# Amplificador.net
KiCad netlist of a schematic drawn in Altium Designer
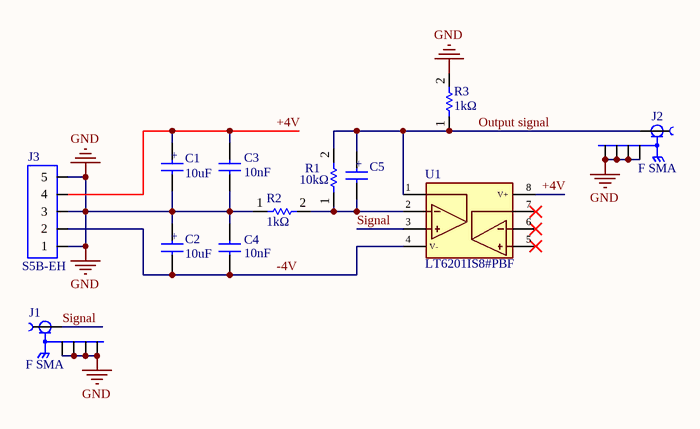
[diagram p0: Amplificador.SchDoc]

(export (version "E")
  (design (tool "Eeschema 10.0.6"))
  (components
    (comp (ref "C1")
      (value "10uF")
      (footprint "WCAP-ATG5_5X11(DXL)")
      (description "10 µF 25 V Aluminum Electrolytic Capacitors Radial, Can 2000 Hrs @ 105°C")
      (libsource (lib "860020472003") (part "WCAP-ATG5_5X11"))
    )
    (comp (ref "C2")
      (value "10uF")
      (footprint "WCAP-ATG5_5X11(DXL)")
      (description "10 µF 25 V Aluminum Electrolytic Capacitors Radial, Can 2000 Hrs @ 105°C")
      (libsource (lib "860020472003") (part "WCAP-ATG5_5X11"))
    )
    (comp (ref "C3")
      (value "10nF")
      (footprint "CAPRR508W54L508T381H660")
      (description "10000 pF ±10% 50V Ceramic Capacitor X7R Radial")
      (libsource (lib "C322C103K5R5TA") (part "C322C103K5R5TA"))
    )
    (comp (ref "C4")
      (value "10nF")
      (footprint "CAPRR508W54L508T381H660")
      (description "10000 pF ±10% 50V Ceramic Capacitor X7R Radial")
      (libsource (lib "C322C103K5R5TA") (part "C322C103K5R5TA"))
    )
    (comp (ref "C5")
      (value "10uF")
      (footprint "WCAP-ATG5_5X11(DXL)")
      (description "10 µF 25 V Aluminum Electrolytic Capacitors Radial, Can 2000 Hrs @ 105°C")
      (libsource (lib "860020472003") (part "WCAP-ATG5_5X11"))
    )
    (comp (ref "J1")
      (value "F SMA")
      (footprint "HUBER+SUHNER_85201239")
      (description "SMA Connector Jack, Female Socket 50 Ohms Through Hole, Right Angle Solder")
      (fields (field (name "MF") "HUBER+SUHNER") (field (name "MP") "85_SMA-50-0-103/111_NE"))
      (libsource (lib "") (part "85201239_1"))
    )
    (comp (ref "J2")
      (value "F SMA")
      (footprint "HUBER+SUHNER_85201239")
      (description "SMA Connector Jack, Female Socket 50 Ohms Through Hole, Right Angle Solder")
      (fields (field (name "MF") "HUBER+SUHNER") (field (name "MP") "85_SMA-50-0-103/111_NE"))
      (libsource (lib "SMA") (part "85201239"))
    )
    (comp (ref "J3")
      (value "S5B-EH")
      (footprint "JST_S5B-EH")
      (description "Connector Header Through Hole, Right Angle 5 position 0.098 (2.50mm)")
      (fields (field (name "MF") "JST Sales"))
      (libsource (lib "S5B-EH") (part "S5B-EH"))
    )
    (comp (ref "R1")
      (value "10kΩ")
      (footprint "RESAD1100W55L630D240B")
      (description "10 kOhms ±1% 0.5W, 1/2W Through Hole Resistor Axial Metal Film")
      (libsource (lib "MFR50SFTE52-10K") (part "10KOhms"))
    )
    (comp (ref "R2")
      (value "1kΩ")
      (footprint "PCBComponent_1")
      (description "1 kOhms ±1% 1W Through Hole Resistor Axial Metal Film")
      (libsource (lib "MFR1WSFBE52-1K") (part "MFR1WSFBE52-1K"))
    )
    (comp (ref "R3")
      (value "1kΩ")
      (footprint "PCBComponent_1")
      (description "1 kOhms ±1% 1W Through Hole Resistor Axial Metal Film")
      (libsource (lib "MFR1WSFBE52-1K") (part "MFR1WSFBE52-1K"))
    )
    (comp (ref "U1")
      (value "LT6201IS8#PBF")
      (footprint "SOIC127P600X175-8N")
      (description "Buffer Amplifier 2 Circuit Rail-to-Rail 8-SO")
      (libsource (lib "LT6201IS8#PBF") (part "LT6201IS8#PBF"))
    )
  )
  (nets
    (net (code "1") (name "/+4V") (class "Default")
      (node (ref "C1") (pin "1") (pinfunction "POS_1") (pintype "passive"))
      (node (ref "C3") (pin "1") (pinfunction "POS_1") (pintype "passive"))
      (node (ref "J3") (pin "4") (pinfunction "4_4") (pintype "passive"))
      (node (ref "U1") (pin "8") (pinfunction "V+_8") (pintype "passive"))
    )
    (net (code "2") (name "/-4V") (class "Default")
      (node (ref "C2") (pin "2") (pinfunction "NEG_2") (pintype "passive"))
      (node (ref "C4") (pin "2") (pinfunction "NEG_2") (pintype "passive"))
      (node (ref "J3") (pin "2") (pinfunction "2_2") (pintype "passive"))
      (node (ref "U1") (pin "4") (pinfunction "V-_4") (pintype "passive"))
    )
    (net (code "3") (name "/Output signal") (class "Default")
      (node (ref "C5") (pin "1") (pinfunction "POS_1") (pintype "passive"))
      (node (ref "J2") (pin "1") (pinfunction "1_1") (pintype "passive"))
      (node (ref "R1") (pin "2") (pinfunction "2_2") (pintype "passive"))
      (node (ref "R3") (pin "1") (pinfunction "1_1") (pintype "passive"))
      (node (ref "U1") (pin "1") (pinfunction "OUTA_1") (pintype "passive"))
    )
    (net (code "4") (name "/Signal") (class "Default")
      (node (ref "J1") (pin "1") (pinfunction "1_1") (pintype "passive"))
      (node (ref "U1") (pin "3") (pinfunction "+INA_3") (pintype "passive"))
    )
    (net (code "5") (name "GND") (class "Default")
      (node (ref "C1") (pin "2") (pinfunction "NEG_2") (pintype "passive"))
      (node (ref "C2") (pin "1") (pinfunction "POS_1") (pintype "passive"))
      (node (ref "C3") (pin "2") (pinfunction "NEG_2") (pintype "passive"))
      (node (ref "C4") (pin "1") (pinfunction "POS_1") (pintype "passive"))
      (node (ref "J1") (pin "G1") (pinfunction "G1_G1") (pintype "power_in"))
      (node (ref "J1") (pin "G2") (pinfunction "G2_G2") (pintype "power_in"))
      (node (ref "J1") (pin "G3") (pinfunction "G3_G3") (pintype "power_in"))
      (node (ref "J1") (pin "G4") (pinfunction "G4_G4") (pintype "power_in"))
      (node (ref "J2") (pin "G1") (pinfunction "G1_G1") (pintype "power_in"))
      (node (ref "J2") (pin "G2") (pinfunction "G2_G2") (pintype "power_in"))
      (node (ref "J2") (pin "G3") (pinfunction "G3_G3") (pintype "power_in"))
      (node (ref "J2") (pin "G4") (pinfunction "G4_G4") (pintype "power_in"))
      (node (ref "J3") (pin "1") (pinfunction "1_1") (pintype "passive"))
      (node (ref "J3") (pin "3") (pinfunction "3_3") (pintype "passive"))
      (node (ref "J3") (pin "5") (pinfunction "5_5") (pintype "passive"))
      (node (ref "R2") (pin "1") (pinfunction "1_1") (pintype "passive"))
      (node (ref "R3") (pin "2") (pinfunction "2_2") (pintype "passive"))
    )
    (net (code "6") (name "Net-(C5-NEG)") (class "Default")
      (node (ref "C5") (pin "2") (pinfunction "NEG_2") (pintype "passive"))
      (node (ref "R1") (pin "1") (pinfunction "1_1") (pintype "passive"))
      (node (ref "R2") (pin "2") (pinfunction "2_2") (pintype "passive"))
      (node (ref "U1") (pin "2") (pinfunction "-INA_2") (pintype "passive"))
    )
    (net (code "7") (name "unconnected-(U1-+INB-Pad5)") (class "Default")
      (node (ref "U1") (pin "5") (pinfunction "+INB_5") (pintype "passive+no_connect"))
    )
    (net (code "8") (name "unconnected-(U1--INB-Pad6)") (class "Default")
      (node (ref "U1") (pin "6") (pinfunction "-INB_6") (pintype "passive+no_connect"))
    )
    (net (code "9") (name "unconnected-(U1-OUTB-Pad7)") (class "Default")
      (node (ref "U1") (pin "7") (pinfunction "OUTB_7") (pintype "passive+no_connect"))
    )
  )
)
